# pipawelbot.net
KiCad netlist of a schematic drawn in EAGLE
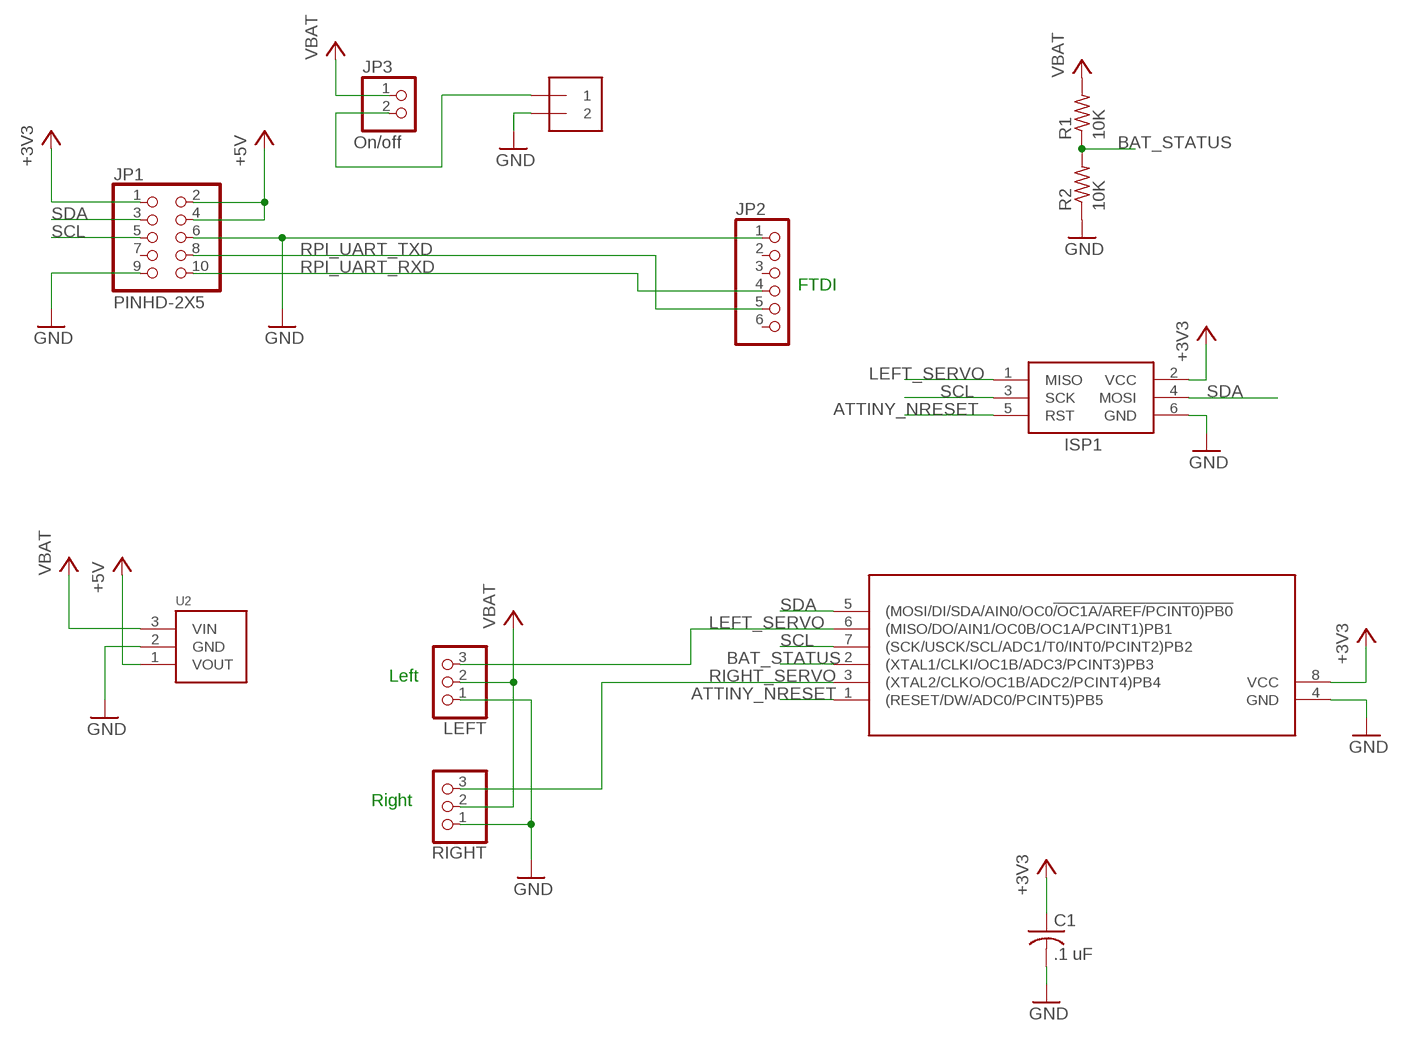
[diagram p0: schematic, sheet 1]

(export (version "E")
  (design (tool "Eeschema 10.0.6"))
  (components
    (comp (ref "C1")
      (value ".1 uF")
      (footprint "eagle-import:C0805")
      (libsource (lib "eagle-import") (part "C-USC0805"))
    )
    (comp (ref "ISP1")
      (value "AVRISP-6")
      (footprint "eagle-import:AVRISP")
      (libsource (lib "eagle-import") (part "AVRISP-6"))
    )
    (comp (ref "J1")
      (value "TERMINAL_BLOCK_1X2-2.54MM")
      (footprint "eagle-import:TERMINAL_BLOCK-1X2-0.1")
      (libsource (lib "eagle-import") (part "TERMINAL_BLOCK_1X2-2.54MM"))
    )
    (comp (ref "JP1")
      (value "PINHD-2X5")
      (footprint "eagle-import:2X5")
      (libsource (lib "eagle-import") (part "PINHD-2X5"))
    )
    (comp (ref "JP2")
      (value "PINHD-1X6")
      (footprint "eagle-import:1X06")
      (libsource (lib "eagle-import") (part "PINHD-1X6"))
    )
    (comp (ref "JP3")
      (value "PINHD-1X2")
      (footprint "eagle-import:1X02")
      (libsource (lib "eagle-import") (part "PINHD-1X2"))
    )
    (comp (ref "LEFT")
      (value "PINHD-1X3")
      (footprint "eagle-import:1X03")
      (libsource (lib "eagle-import") (part "PINHD-1X3"))
    )
    (comp (ref "R1")
      (value "10K")
      (footprint "eagle-import:R0805")
      (libsource (lib "eagle-import") (part "R-US_R0805"))
    )
    (comp (ref "R2")
      (value "10K")
      (footprint "eagle-import:R0805")
      (libsource (lib "eagle-import") (part "R-US_R0805"))
    )
    (comp (ref "RIGHT")
      (value "PINHD-1X3")
      (footprint "eagle-import:1X03")
      (libsource (lib "eagle-import") (part "PINHD-1X3"))
    )
    (comp (ref "U1")
      (value "ATTINY85")
      (footprint "eagle-import:DIL08")
      (libsource (lib "eagle-import") (part "ATTINY85"))
    )
    (comp (ref "U2")
      (value "S7V7F5")
      (footprint "eagle-import:POLOLU-REG")
      (libsource (lib "eagle-import") (part "S7V7F5"))
    )
  )
  (nets
    (net (code "1") (name "+3V3") (class "Default")
      (node (ref "C1") (pin "1") (pinfunction "1_1") (pintype "passive"))
      (node (ref "ISP1") (pin "2") (pinfunction "VCC_2") (pintype "power_in"))
      (node (ref "JP1") (pin "1") (pinfunction "1_1") (pintype "passive"))
      (node (ref "U1") (pin "8") (pinfunction "VCC_8") (pintype "power_in"))
    )
    (net (code "2") (name "+5V") (class "Default")
      (node (ref "JP1") (pin "2") (pinfunction "2_2") (pintype "passive"))
      (node (ref "JP1") (pin "4") (pinfunction "4_4") (pintype "passive"))
      (node (ref "U2") (pin "1") (pinfunction "VOUT_1") (pintype "bidirectional"))
    )
    (net (code "3") (name "/ATTINY_NRESET") (class "Default")
      (node (ref "ISP1") (pin "5") (pinfunction "RST_5") (pintype "output"))
      (node (ref "U1") (pin "1") (pinfunction "(RESET/DW/ADC0/PCINT5)PB5_1") (pintype "bidirectional"))
    )
    (net (code "4") (name "/BAT_STATUS") (class "Default")
      (node (ref "R1") (pin "1") (pinfunction "1_1") (pintype "passive"))
      (node (ref "R2") (pin "2") (pinfunction "2_2") (pintype "passive"))
      (node (ref "U1") (pin "2") (pinfunction "(XTAL1/CLKI/OC1B/ADC3/PCINT3)PB3_2") (pintype "bidirectional"))
    )
    (net (code "5") (name "/LEFT_SERVO") (class "Default")
      (node (ref "ISP1") (pin "1") (pinfunction "MISO_1") (pintype "input"))
      (node (ref "LEFT") (pin "3") (pinfunction "3_3") (pintype "passive"))
      (node (ref "U1") (pin "6") (pinfunction "(MISO/DO/AIN1/OC0B/OC1A/PCINT1)PB1_6") (pintype "bidirectional"))
    )
    (net (code "6") (name "/RIGHT_SERVO") (class "Default")
      (node (ref "RIGHT") (pin "3") (pinfunction "3_3") (pintype "passive"))
      (node (ref "U1") (pin "3") (pinfunction "(XTAL2/CLKO/OC1B/ADC2/PCINT4)PB4_3") (pintype "bidirectional"))
    )
    (net (code "7") (name "/RPI_UART_RXD") (class "Default")
      (node (ref "JP1") (pin "10") (pinfunction "10_10") (pintype "passive"))
      (node (ref "JP2") (pin "4") (pinfunction "4_4") (pintype "passive"))
    )
    (net (code "8") (name "/RPI_UART_TXD") (class "Default")
      (node (ref "JP1") (pin "8") (pinfunction "8_8") (pintype "passive"))
      (node (ref "JP2") (pin "5") (pinfunction "5_5") (pintype "passive"))
    )
    (net (code "9") (name "/SCL") (class "Default")
      (node (ref "ISP1") (pin "3") (pinfunction "SCK_3") (pintype "output"))
      (node (ref "JP1") (pin "5") (pinfunction "5_5") (pintype "passive"))
      (node (ref "U1") (pin "7") (pinfunction "(SCK/USCK/SCL/ADC1/T0/INT0/PCINT2)PB2_7") (pintype "bidirectional"))
    )
    (net (code "10") (name "/SDA") (class "Default")
      (node (ref "ISP1") (pin "4") (pinfunction "MOSI_4") (pintype "output"))
      (node (ref "JP1") (pin "3") (pinfunction "3_3") (pintype "passive"))
      (node (ref "U1") (pin "5") (pinfunction "(MOSI/DI/SDA/AIN0/OC0~{/OC1A/AREF/PCINT0})PB0_5") (pintype "bidirectional"))
    )
    (net (code "11") (name "GND") (class "Default")
      (node (ref "C1") (pin "2") (pinfunction "2_2") (pintype "passive"))
      (node (ref "ISP1") (pin "6") (pinfunction "GND_6") (pintype "power_in"))
      (node (ref "J1") (pin "1") (pinfunction "2_1") (pintype "passive"))
      (node (ref "JP1") (pin "6") (pinfunction "6_6") (pintype "passive"))
      (node (ref "JP1") (pin "9") (pinfunction "9_9") (pintype "passive"))
      (node (ref "JP2") (pin "1") (pinfunction "1_1") (pintype "passive"))
      (node (ref "LEFT") (pin "1") (pinfunction "1_1") (pintype "passive"))
      (node (ref "R2") (pin "1") (pinfunction "1_1") (pintype "passive"))
      (node (ref "RIGHT") (pin "1") (pinfunction "1_1") (pintype "passive"))
      (node (ref "U1") (pin "4") (pinfunction "GND_4") (pintype "power_in"))
      (node (ref "U2") (pin "2") (pinfunction "GND_2") (pintype "power_in"))
    )
    (net (code "12") (name "Net-(J1-1)") (class "Default")
      (node (ref "J1") (pin "2") (pinfunction "1_2") (pintype "passive"))
      (node (ref "JP3") (pin "2") (pinfunction "2_2") (pintype "passive"))
    )
    (net (code "13") (name "VBAT") (class "Default")
      (node (ref "JP3") (pin "1") (pinfunction "1_1") (pintype "passive"))
      (node (ref "LEFT") (pin "2") (pinfunction "2_2") (pintype "passive"))
      (node (ref "R1") (pin "2") (pinfunction "2_2") (pintype "passive"))
      (node (ref "RIGHT") (pin "2") (pinfunction "2_2") (pintype "passive"))
      (node (ref "U2") (pin "3") (pinfunction "VIN_3") (pintype "bidirectional"))
    )
    (net (code "14") (name "unconnected-(JP1-Pad7)") (class "Default")
      (node (ref "JP1") (pin "7") (pinfunction "7_7") (pintype "passive"))
    )
    (net (code "15") (name "unconnected-(JP2-Pad2)") (class "Default")
      (node (ref "JP2") (pin "2") (pinfunction "2_2") (pintype "passive"))
    )
    (net (code "16") (name "unconnected-(JP2-Pad3)") (class "Default")
      (node (ref "JP2") (pin "3") (pinfunction "3_3") (pintype "passive"))
    )
    (net (code "17") (name "unconnected-(JP2-Pad6)") (class "Default")
      (node (ref "JP2") (pin "6") (pinfunction "6_6") (pintype "passive"))
    )
  )
)
